# smartee_periph.net
KiCad netlist of a schematic drawn in Altium Designer
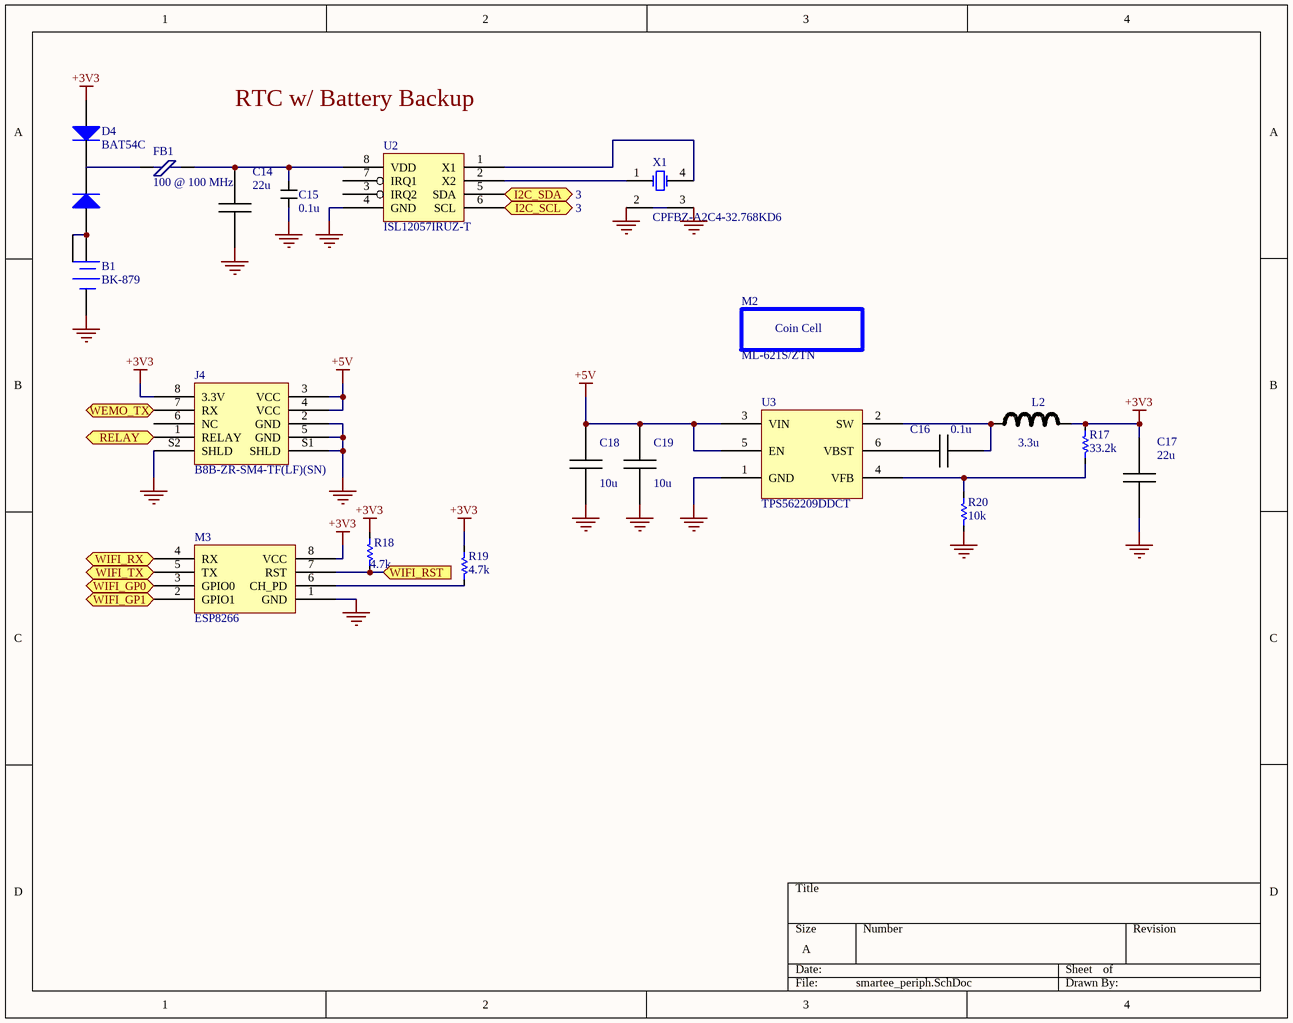
[diagram p0: smartee_periph.SchDoc]

(export (version "E")
  (design (tool "Eeschema 10.0.6"))
  (components
    (comp (ref "B1")
      (value "BK-879")
      (footprint "BK-879")
      (description "HOLDER 6.8MM COIN CELL SMD")
      (fields (field (name "MANUFACTURER") "MPD (Memory Protection Devices)"))
      (libsource (lib "NILM Library") (part "BK-879"))
    )
    (comp (ref "C14")
      (value "22u")
      (footprint "0805")
      (description "CAP CER 22UF 25V 20% X5R 0805")
      (fields
        (field (name "MANUFACTURER") "Samsung Electro-Mechanics America, Inc")
        (field (name "MANUFACTURER PART NUMBER") "CL21A226MAQNNNE")
      )
      (libsource (lib "NILM Library") (part "CL21A226MAQNNNE"))
    )
    (comp (ref "C15")
      (value "0.1u")
      (footprint "R0603")
      (description "CAP CER 0.1UF 50V Y5V 0603")
      (fields
        (field (name "MANUFACTURER") "Yageo")
        (field (name "MANUFACTURER PART NUMBER") "CC0603ZRY5V9BB104")
      )
      (libsource (lib "NILM Library") (part "CC0603ZRY5V9BB104"))
    )
    (comp (ref "C16")
      (value "0.1u")
      (footprint "0805")
      (description "CAP CER 0.1UF 25V 10% X7R 0805")
      (fields
        (field (name "MANUFACTURER") "AVX Corporation")
        (field (name "MANUFACTURER PART NUMBER") "08053C104KAT2A")
      )
      (libsource (lib "NILM Library") (part "08053C104KAT2A"))
    )
    (comp (ref "C17")
      (value "22u")
      (footprint "1206")
      (description "CAP CER 22UF 6.3V 10% X5R 1206")
      (fields
        (field (name "MANUFACTURER") "TDK Corporation")
        (field (name "MANUFACTURER PART NUMBER") "C3216X5R0J226K/1.6")
      )
      (libsource (lib "NILM Library") (part "C3216X5R0J226K/1.6"))
    )
    (comp (ref "C18")
      (value "10u")
      (footprint "0805")
      (description "CAP CER 10UF 10V 10% X5R 0805")
      (fields
        (field (name "MANUFACTURER") "Kemet")
        (field (name "MANUFACTURER PART NUMBER") "C0805C106K8PACTU")
      )
      (libsource (lib "NILM Library") (part "C0805C106K8PACTU"))
    )
    (comp (ref "C19")
      (value "10u")
      (footprint "0805")
      (description "CAP CER 10UF 10V 10% X5R 0805")
      (fields
        (field (name "MANUFACTURER") "Kemet")
        (field (name "MANUFACTURER PART NUMBER") "C0805C106K8PACTU")
      )
      (libsource (lib "NILM Library") (part "C0805C106K8PACTU"))
    )
    (comp (ref "D4")
      (value "BAT54C")
      (footprint "SOT23")
      (description "DIODE SCHOTTKY 30V 200MA SOT23")
      (fields (field (name "MANUFACTURER") "Fairchild Semiconductor"))
      (libsource (lib "NILM Library") (part "BAT54C"))
    )
    (comp (ref "FB1")
      (value "100 @ 100 MHz")
      (footprint "0603")
      (description "FERRITE CHIP 100 OHM 3A 0603")
      (fields
        (field (name "MANUFACTURER") "TDK Corporation")
        (field (name "MANUFACTURER PART NUMBER") "MPZ1608S101ATAH0")
      )
      (libsource (lib "NILM Library") (part "MPZ1608S101ATAH0"))
    )
    (comp (ref "J4")
      (value "B8B-ZR-SM4-TF(LF)(SN)")
      (footprint "B8B-ZR-SM4-TF")
      (description "CONN HEADER ZH TOP 8POS 1.5MM")
      (fields (field (name "MANUFACTURER") "JST Sales America Inc"))
      (libsource (lib "NILM Library") (part "B8B-ZR-SM4-TF(LF)(SN)"))
    )
    (comp (ref "L2")
      (value "3.3u")
      (footprint "0805")
      (description "FIXED IND 3.3UH 900MA 190 MOHM")
      (fields
        (field (name "MANUFACTURER") "TDK Corporation")
        (field (name "MANUFACTURER PART NUMBER") "MLP2012S3R3MT0S1")
      )
      (libsource (lib "NILM Library") (part "MLP2012S3R3MT0S1"))
    )
    (comp (ref "M2")
      (value "ML-621S/ZTN")
      (description "BATTERY LITHIUM 3V RECHARGE")
      (fields (field (name "MANUFACTURER") "Panasonic - BSG"))
      (libsource (lib "NILM Library") (part "ML-621S/ZTN"))
    )
    (comp (ref "M3")
      (value "ESP8266")
      (footprint "ESP8266")
      (description "WiFi UART module")
      (libsource (lib "NILM Library") (part "ESP8266"))
    )
    (comp (ref "R17")
      (value "33.2k")
      (footprint "0603")
      (description "Resistor")
      (fields (field (name "Comment") "RES") (field (name "PUBLISHER") "Altium Limited"))
      (libsource (lib "nilm") (part "RES"))
    )
    (comp (ref "R18")
      (value "4.7k")
      (footprint "0603")
      (description "Resistor")
      (fields (field (name "Comment") "RES") (field (name "PUBLISHER") "Altium Limited"))
      (libsource (lib "nilm") (part "RES"))
    )
    (comp (ref "R19")
      (value "4.7k")
      (footprint "0603")
      (description "Resistor")
      (fields (field (name "Comment") "RES") (field (name "PUBLISHER") "Altium Limited"))
      (libsource (lib "nilm") (part "RES"))
    )
    (comp (ref "R20")
      (value "10k")
      (footprint "0603")
      (description "Resistor")
      (fields (field (name "Comment") "RES") (field (name "PUBLISHER") "Altium Limited"))
      (libsource (lib "nilm") (part "RES"))
    )
    (comp (ref "U2")
      (value "ISL12057IRUZ-T")
      (footprint "UTDFN8")
      (description "IC RTC CLK/CALENDAR I2C 8-UTDFN")
      (fields (field (name "MANUFACTURER") "Intersil"))
      (libsource (lib "NILM Library") (part "ISL12057IRUZ-T"))
    )
    (comp (ref "U3")
      (value "TPS562209DDCT")
      (footprint "TSOP-6")
      (description "IC REG BUCK SYNC ADJ 2A SOT-23-6")
      (fields (field (name "MANUFACTURER") "Texas Instruments"))
      (libsource (lib "NILM Library") (part "TPS562209DDCT"))
    )
    (comp (ref "X1")
      (value "CPFBZ-A2C4-32.768KD6")
      (footprint "XTAL")
      (description "CRYSTAL 32.768KHZ 6PF SMD")
      (fields (field (name "MANUFACTURER") "Cardinal Components Inc."))
      (libsource (lib "NILM Library") (part "CPFBZ-A2C4-32.768KD6"))
    )
  )
  (nets
    (net (code "1") (name "+3V3") (class "Default")
      (node (ref "C17") (pin "1") (pinfunction "1_1") (pintype "passive"))
      (node (ref "D4") (pin "2") (pinfunction "A2_2") (pintype "passive"))
      (node (ref "J4") (pin "8") (pinfunction "3.3V_8") (pintype "passive"))
      (node (ref "L2") (pin "2") (pinfunction "2_2") (pintype "passive"))
      (node (ref "M3") (pin "8") (pinfunction "VCC_8") (pintype "passive"))
      (node (ref "R17") (pin "1") (pinfunction "1_1") (pintype "passive"))
      (node (ref "R18") (pin "1") (pinfunction "1_1") (pintype "passive"))
      (node (ref "R19") (pin "1") (pinfunction "1_1") (pintype "passive"))
    )
    (net (code "2") (name "+5V") (class "Default")
      (node (ref "C18") (pin "1") (pinfunction "1_1") (pintype "passive"))
      (node (ref "C19") (pin "1") (pinfunction "1_1") (pintype "passive"))
      (node (ref "J4") (pin "3") (pinfunction "VCC_3") (pintype "passive"))
      (node (ref "J4") (pin "4") (pinfunction "VCC_4") (pintype "passive"))
      (node (ref "U3") (pin "3") (pinfunction "VIN_3") (pintype "passive"))
      (node (ref "U3") (pin "5") (pinfunction "EN_5") (pintype "passive"))
    )
    (net (code "3") (name "/I2C_SCL") (class "Default")
      (node (ref "U2") (pin "6") (pinfunction "SCL_6") (pintype "passive"))
    )
    (net (code "4") (name "/I2C_SDA") (class "Default")
      (node (ref "U2") (pin "5") (pinfunction "SDA_5") (pintype "passive"))
    )
    (net (code "5") (name "/RELAY") (class "Default")
      (node (ref "J4") (pin "1") (pinfunction "RELAY_1") (pintype "passive"))
    )
    (net (code "6") (name "/WEMO_TX") (class "Default")
      (node (ref "J4") (pin "7") (pinfunction "RX_7") (pintype "passive"))
    )
    (net (code "7") (name "/WIFI_GP0") (class "Default")
      (node (ref "M3") (pin "3") (pinfunction "GPIO0_3") (pintype "passive"))
    )
    (net (code "8") (name "/WIFI_GP1") (class "Default")
      (node (ref "M3") (pin "2") (pinfunction "GPIO1_2") (pintype "passive"))
    )
    (net (code "9") (name "/WIFI_RST") (class "Default")
      (node (ref "M3") (pin "7") (pinfunction "RST_7") (pintype "passive"))
      (node (ref "R18") (pin "2") (pinfunction "2_2") (pintype "passive"))
    )
    (net (code "10") (name "/WIFI_RX") (class "Default")
      (node (ref "M3") (pin "4") (pinfunction "RX_4") (pintype "passive"))
    )
    (net (code "11") (name "/WIFI_TX") (class "Default")
      (node (ref "M3") (pin "5") (pinfunction "TX_5") (pintype "passive"))
    )
    (net (code "12") (name "GND") (class "Default")
      (node (ref "B1") (pin "N") (pinfunction "N_N") (pintype "passive"))
      (node (ref "C14") (pin "2") (pinfunction "2_2") (pintype "passive"))
      (node (ref "C15") (pin "2") (pinfunction "2_2") (pintype "passive"))
      (node (ref "C17") (pin "2") (pinfunction "2_2") (pintype "passive"))
      (node (ref "C18") (pin "2") (pinfunction "2_2") (pintype "passive"))
      (node (ref "C19") (pin "2") (pinfunction "2_2") (pintype "passive"))
      (node (ref "J4") (pin "2") (pinfunction "GND_2") (pintype "passive"))
      (node (ref "J4") (pin "5") (pinfunction "GND_5") (pintype "passive"))
      (node (ref "J4") (pin "S1") (pinfunction "SHLD_S1") (pintype "passive"))
      (node (ref "J4") (pin "S2") (pinfunction "SHLD_S2") (pintype "passive"))
      (node (ref "M3") (pin "1") (pinfunction "GND_1") (pintype "passive"))
      (node (ref "R20") (pin "2") (pinfunction "2_2") (pintype "passive"))
      (node (ref "U2") (pin "4") (pinfunction "GND_4") (pintype "passive"))
      (node (ref "U3") (pin "1") (pinfunction "GND_1") (pintype "passive"))
      (node (ref "X1") (pin "2") (pinfunction "2_2") (pintype "passive"))
      (node (ref "X1") (pin "3") (pinfunction "3_3") (pintype "passive"))
    )
    (net (code "13") (name "Net-(D4-A1)") (class "Default")
      (node (ref "B1") (pin "P1") (pinfunction "P1_P1") (pintype "passive"))
      (node (ref "B1") (pin "P2") (pinfunction "P2_P2") (pintype "passive"))
      (node (ref "D4") (pin "1") (pinfunction "A1_1") (pintype "passive"))
    )
    (net (code "14") (name "Net-(D4-K)") (class "Default")
      (node (ref "D4") (pin "3") (pinfunction "K_3") (pintype "passive"))
      (node (ref "FB1") (pin "1") (pinfunction "1_1") (pintype "passive"))
    )
    (net (code "15") (name "Net-(M3-CH_PD)") (class "Default")
      (node (ref "M3") (pin "6") (pinfunction "CH_PD_6") (pintype "passive"))
      (node (ref "R19") (pin "2") (pinfunction "2_2") (pintype "passive"))
    )
    (net (code "16") (name "Net-(U2-VDD)") (class "Default")
      (node (ref "C14") (pin "1") (pinfunction "1_1") (pintype "passive"))
      (node (ref "C15") (pin "1") (pinfunction "1_1") (pintype "passive"))
      (node (ref "FB1") (pin "2") (pinfunction "2_2") (pintype "passive"))
      (node (ref "U2") (pin "8") (pinfunction "VDD_8") (pintype "passive"))
    )
    (net (code "17") (name "Net-(U2-X1)") (class "Default")
      (node (ref "U2") (pin "1") (pinfunction "X1_1") (pintype "passive"))
      (node (ref "X1") (pin "4") (pinfunction "4_4") (pintype "passive"))
    )
    (net (code "18") (name "Net-(U2-X2)") (class "Default")
      (node (ref "U2") (pin "2") (pinfunction "X2_2") (pintype "passive"))
      (node (ref "X1") (pin "1") (pinfunction "OSC1_1") (pintype "passive"))
    )
    (net (code "19") (name "Net-(U3-SW)") (class "Default")
      (node (ref "C16") (pin "2") (pinfunction "2_2") (pintype "passive"))
      (node (ref "L2") (pin "1") (pinfunction "1_1") (pintype "passive"))
      (node (ref "U3") (pin "2") (pinfunction "SW_2") (pintype "passive"))
    )
    (net (code "20") (name "Net-(U3-VBST)") (class "Default")
      (node (ref "C16") (pin "1") (pinfunction "1_1") (pintype "passive"))
      (node (ref "U3") (pin "6") (pinfunction "VBST_6") (pintype "passive"))
    )
    (net (code "21") (name "Net-(U3-VFB)") (class "Default")
      (node (ref "R17") (pin "2") (pinfunction "2_2") (pintype "passive"))
      (node (ref "R20") (pin "1") (pinfunction "1_1") (pintype "passive"))
      (node (ref "U3") (pin "4") (pinfunction "VFB_4") (pintype "passive"))
    )
    (net (code "22") (name "unconnected-(J4-NC-Pad6)") (class "Default")
      (node (ref "J4") (pin "6") (pinfunction "NC_6") (pintype "passive"))
    )
    (net (code "23") (name "unconnected-(U2-IRQ1-Pad7)") (class "Default")
      (node (ref "U2") (pin "7") (pinfunction "IRQ1_7") (pintype "passive"))
    )
    (net (code "24") (name "unconnected-(U2-IRQ2-Pad3)") (class "Default")
      (node (ref "U2") (pin "3") (pinfunction "IRQ2_3") (pintype "passive"))
    )
  )
)
